# 03_-_LED7SEG.net
KiCad netlist of a schematic drawn in Altium Designer
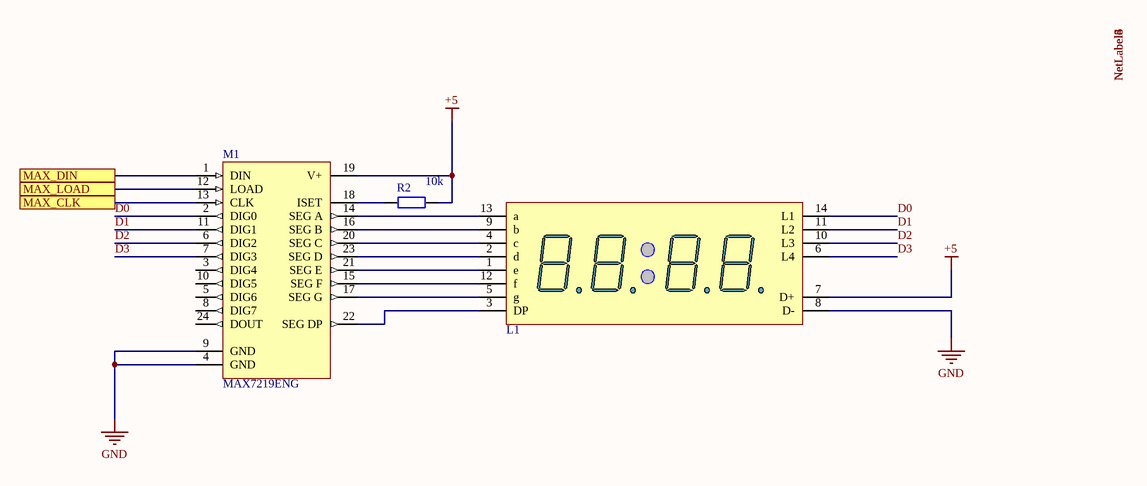
[diagram p0: [03] - LED7SEG.SchDoc]

(export (version "E")
  (design (tool "Eeschema 10.0.6"))
  (components
    (comp (ref "L1")
      (value "Led 7 Seg 4 digit - Anode")
      (footprint "LED7SEG-4-0.56-RG")
      (libsource (lib "My Library") (part "LED7SEG-4-RG"))
    )
    (comp (ref "M1")
      (value "MAX7219ENG")
      (footprint "DIP24/W0.3")
      (description "Serially Interfaced, 8-Digit LED Display Driver")
      (fields (field (name "PUBLISHER") "Altium Limited"))
      (libsource (lib "My Library") (part "MAX7219ENG"))
    )
    (comp (ref "R2")
      (value "10k")
      (footprint "RES_SMD_0805")
      (description "Resistor 1/4W")
      (libsource (lib "My Library") (part "R1/4W"))
    )
  )
  (nets
    (net (code "1") (name "+5") (class "Default")
      (node (ref "L1") (pin "7") (pinfunction "D+_7") (pintype "passive"))
      (node (ref "M1") (pin "19") (pinfunction "V+_19") (pintype "power_in"))
      (node (ref "R2") (pin "2") (pinfunction "2_2") (pintype "passive"))
    )
    (net (code "2") (name "/D0") (class "Default")
      (node (ref "L1") (pin "14") (pinfunction "L1_14") (pintype "passive"))
      (node (ref "M1") (pin "2") (pinfunction "DIG0_2") (pintype "output"))
    )
    (net (code "3") (name "/D1") (class "Default")
      (node (ref "L1") (pin "11") (pinfunction "L2_11") (pintype "passive"))
      (node (ref "M1") (pin "11") (pinfunction "DIG1_11") (pintype "output"))
    )
    (net (code "4") (name "/D2") (class "Default")
      (node (ref "L1") (pin "10") (pinfunction "L3_10") (pintype "passive"))
      (node (ref "M1") (pin "6") (pinfunction "DIG2_6") (pintype "output"))
    )
    (net (code "5") (name "/D3") (class "Default")
      (node (ref "L1") (pin "6") (pinfunction "L4_6") (pintype "passive"))
      (node (ref "M1") (pin "7") (pinfunction "DIG3_7") (pintype "output"))
    )
    (net (code "6") (name "/MAX_CLK") (class "Default")
      (node (ref "M1") (pin "13") (pinfunction "CLK_13") (pintype "input"))
    )
    (net (code "7") (name "/MAX_DIN") (class "Default")
      (node (ref "M1") (pin "1") (pinfunction "DIN_1") (pintype "input"))
    )
    (net (code "8") (name "/MAX_LOAD") (class "Default")
      (node (ref "M1") (pin "12") (pinfunction "LOAD_12") (pintype "input"))
    )
    (net (code "10") (name "GND") (class "Default")
      (node (ref "L1") (pin "8") (pinfunction "D-_8") (pintype "passive"))
      (node (ref "M1") (pin "4") (pinfunction "GND_4") (pintype "power_in"))
      (node (ref "M1") (pin "9") (pinfunction "GND_9") (pintype "power_in"))
    )
    (net (code "11") (name "Net-(L1-DP)") (class "Default")
      (node (ref "L1") (pin "3") (pinfunction "DP_3") (pintype "passive"))
      (node (ref "M1") (pin "22") (pinfunction "SEG_DP_22") (pintype "output"))
    )
    (net (code "12") (name "Net-(L1-a)") (class "Default")
      (node (ref "L1") (pin "13") (pinfunction "a_13") (pintype "passive"))
      (node (ref "M1") (pin "14") (pinfunction "SEG_A_14") (pintype "output"))
    )
    (net (code "13") (name "Net-(L1-b)") (class "Default")
      (node (ref "L1") (pin "9") (pinfunction "b_9") (pintype "passive"))
      (node (ref "M1") (pin "16") (pinfunction "SEG_B_16") (pintype "output"))
    )
    (net (code "14") (name "Net-(L1-c)") (class "Default")
      (node (ref "L1") (pin "4") (pinfunction "c_4") (pintype "passive"))
      (node (ref "M1") (pin "20") (pinfunction "SEG_C_20") (pintype "output"))
    )
    (net (code "15") (name "Net-(L1-d)") (class "Default")
      (node (ref "L1") (pin "2") (pinfunction "d_2") (pintype "passive"))
      (node (ref "M1") (pin "23") (pinfunction "SEG_D_23") (pintype "output"))
    )
    (net (code "16") (name "Net-(L1-e)") (class "Default")
      (node (ref "L1") (pin "1") (pinfunction "e_1") (pintype "passive"))
      (node (ref "M1") (pin "21") (pinfunction "SEG_E_21") (pintype "output"))
    )
    (net (code "17") (name "Net-(L1-f)") (class "Default")
      (node (ref "L1") (pin "12") (pinfunction "f_12") (pintype "passive"))
      (node (ref "M1") (pin "15") (pinfunction "SEG_F_15") (pintype "output"))
    )
    (net (code "18") (name "Net-(L1-g)") (class "Default")
      (node (ref "L1") (pin "5") (pinfunction "g_5") (pintype "passive"))
      (node (ref "M1") (pin "17") (pinfunction "SEG_G_17") (pintype "output"))
    )
    (net (code "19") (name "Net-(M1-ISET)") (class "Default")
      (node (ref "M1") (pin "18") (pinfunction "ISET_18") (pintype "passive"))
      (node (ref "R2") (pin "1") (pinfunction "1_1") (pintype "passive"))
    )
    (net (code "20") (name "unconnected-(M1-DIG4-Pad3)") (class "Default")
      (node (ref "M1") (pin "3") (pinfunction "DIG4_3") (pintype "output"))
    )
    (net (code "21") (name "unconnected-(M1-DIG5-Pad10)") (class "Default")
      (node (ref "M1") (pin "10") (pinfunction "DIG5_10") (pintype "output"))
    )
    (net (code "22") (name "unconnected-(M1-DIG6-Pad5)") (class "Default")
      (node (ref "M1") (pin "5") (pinfunction "DIG6_5") (pintype "output"))
    )
    (net (code "23") (name "unconnected-(M1-DIG7-Pad8)") (class "Default")
      (node (ref "M1") (pin "8") (pinfunction "DIG7_8") (pintype "output"))
    )
    (net (code "24") (name "unconnected-(M1-DOUT-Pad24)") (class "Default")
      (node (ref "M1") (pin "24") (pinfunction "DOUT_24") (pintype "output"))
    )
  )
)
